# GYBHDHT.net
KiCad netlist of a schematic drawn in Altium Designer
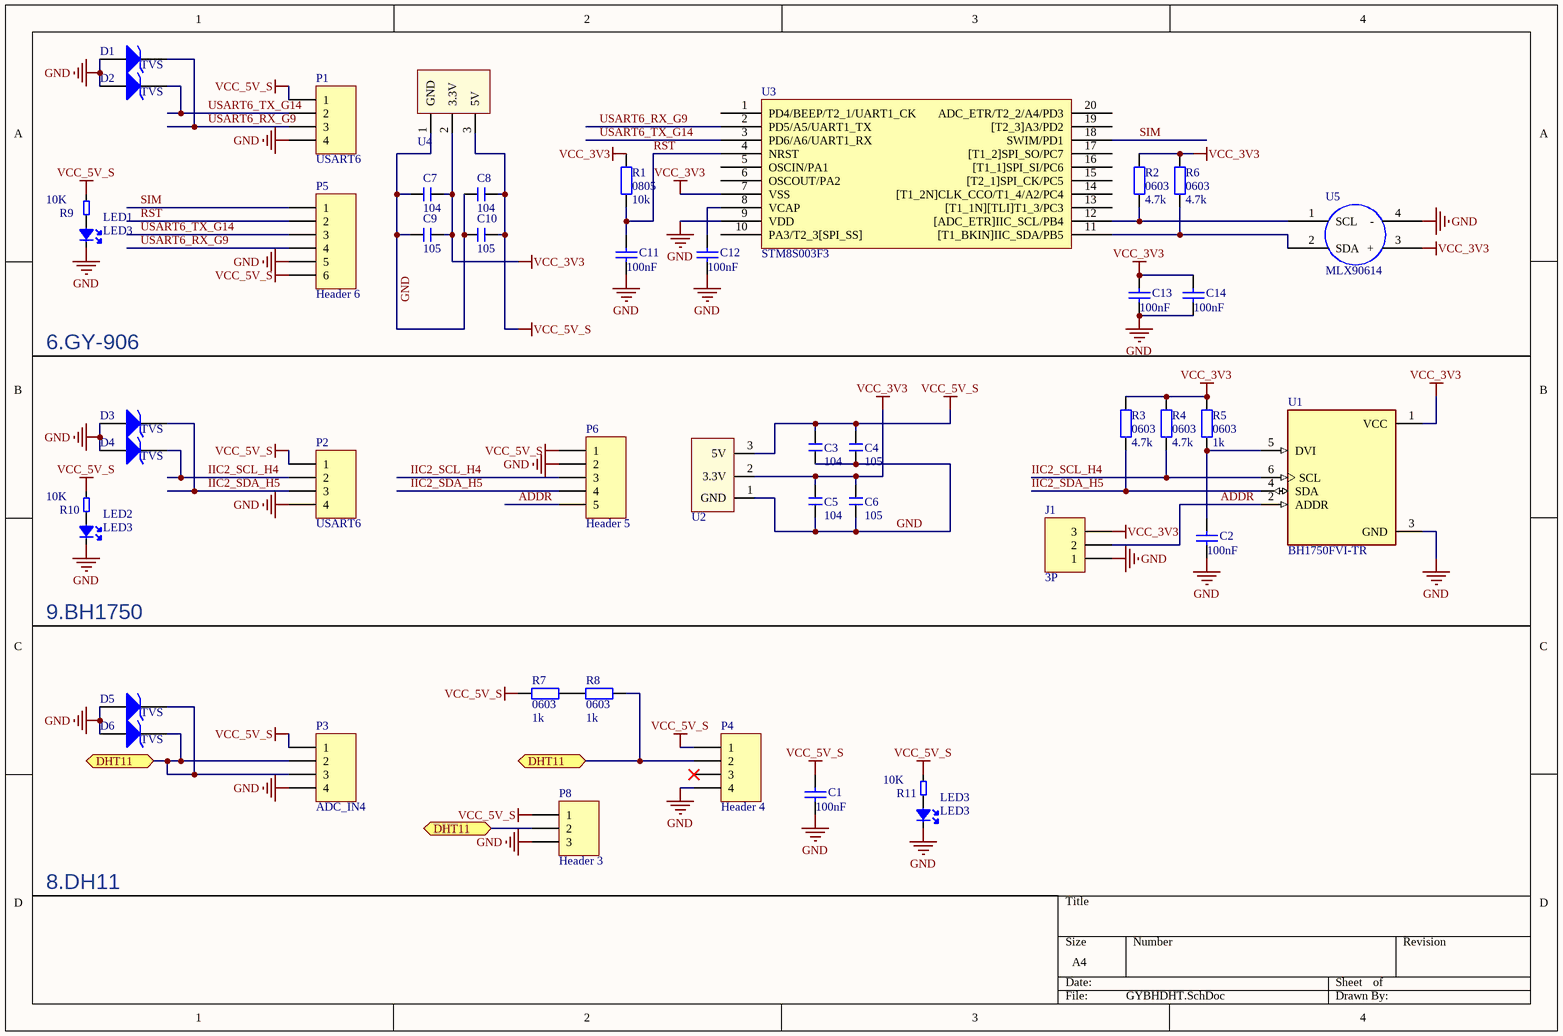
[diagram p0: GYBHDHT.SchDoc]

(export (version "E")
  (design (tool "Eeschema 10.0.6"))
  (components
    (comp (ref "C1")
      (value "100nF")
      (footprint "C 0603_L")
      (fields (field (name "Comment") "CAP"))
      (libsource (lib "QT") (part "CAP"))
    )
    (comp (ref "C2")
      (value "100nF")
      (footprint "C 0603_L")
      (fields (field (name "Comment") "CAP"))
      (libsource (lib "QT") (part "CAP"))
    )
    (comp (ref "C3")
      (value "104")
      (footprint "C 0603")
      (description "无极性贴片电容")
      (fields (field (name "版权归属") "源创客"))
      (libsource (lib "电阻-电容-电感") (part "C"))
    )
    (comp (ref "C4")
      (value "105")
      (footprint "C 0603")
      (description "无极性贴片电容")
      (fields (field (name "版权归属") "源创客"))
      (libsource (lib "电阻-电容-电感") (part "C"))
    )
    (comp (ref "C5")
      (value "104")
      (footprint "C 0603")
      (description "无极性贴片电容")
      (fields (field (name "版权归属") "源创客"))
      (libsource (lib "电阻-电容-电感") (part "C"))
    )
    (comp (ref "C6")
      (value "105")
      (footprint "C 0603")
      (description "无极性贴片电容")
      (fields (field (name "版权归属") "源创客"))
      (libsource (lib "电阻-电容-电感") (part "C"))
    )
    (comp (ref "C7")
      (value "104")
      (footprint "C 0603")
      (description "无极性贴片电容")
      (fields (field (name "版权归属") "源创客"))
      (libsource (lib "电阻-电容-电感") (part "C"))
    )
    (comp (ref "C8")
      (value "104")
      (footprint "C 0603")
      (description "无极性贴片电容")
      (fields (field (name "版权归属") "源创客"))
      (libsource (lib "电阻-电容-电感") (part "C"))
    )
    (comp (ref "C9")
      (value "105")
      (footprint "C 0603")
      (description "无极性贴片电容")
      (fields (field (name "版权归属") "源创客"))
      (libsource (lib "电阻-电容-电感") (part "C"))
    )
    (comp (ref "C10")
      (value "105")
      (footprint "C 0603")
      (description "无极性贴片电容")
      (fields (field (name "版权归属") "源创客"))
      (libsource (lib "电阻-电容-电感") (part "C"))
    )
    (comp (ref "C11")
      (value "100nF")
      (footprint "C 0603_L")
      (fields (field (name "Comment") "CAP"))
      (libsource (lib "QT") (part "CAP"))
    )
    (comp (ref "C12")
      (value "100nF")
      (footprint "C 0603_M")
      (fields (field (name "Comment") "CAP"))
      (libsource (lib "QT") (part "CAP"))
    )
    (comp (ref "C13")
      (value "100nF")
      (footprint "C 0603_M")
      (fields (field (name "Comment") "CAP"))
      (libsource (lib "QT") (part "CAP"))
    )
    (comp (ref "C14")
      (value "100nF")
      (footprint "C 0603_M")
      (fields (field (name "Comment") "CAP"))
      (libsource (lib "QT") (part "CAP"))
    )
    (comp (ref "D1")
      (value "TVS")
      (footprint "SOD-523")
      (description "High Conductance Fast Diode")
      (fields (field (name "PUBLISHER") "Altium Limited"))
      (libsource (lib "QT") (part "D"))
    )
    (comp (ref "D2")
      (value "TVS")
      (footprint "SOD-523")
      (description "High Conductance Fast Diode")
      (fields (field (name "PUBLISHER") "Altium Limited"))
      (libsource (lib "QT") (part "D"))
    )
    (comp (ref "D3")
      (value "TVS")
      (footprint "SOD-523")
      (description "High Conductance Fast Diode")
      (fields (field (name "PUBLISHER") "Altium Limited"))
      (libsource (lib "QT") (part "D"))
    )
    (comp (ref "D4")
      (value "TVS")
      (footprint "SOD-523")
      (description "High Conductance Fast Diode")
      (fields (field (name "PUBLISHER") "Altium Limited"))
      (libsource (lib "QT") (part "D"))
    )
    (comp (ref "D5")
      (value "TVS")
      (footprint "SOD-523")
      (description "High Conductance Fast Diode")
      (fields (field (name "PUBLISHER") "Altium Limited"))
      (libsource (lib "QT") (part "D"))
    )
    (comp (ref "D6")
      (value "TVS")
      (footprint "SOD-523")
      (description "High Conductance Fast Diode")
      (fields (field (name "PUBLISHER") "Altium Limited"))
      (libsource (lib "QT") (part "D"))
    )
    (comp (ref "J1") (value "3P") (footprint "3P") (libsource (lib "F1C100S") (part "3P")))
    (comp (ref "LED1")
      (value "LED3")
      (footprint "0603-led")
      (description "DIODE LED")
      (libsource (lib "HXT-SCH") (part "CP_DIOLED"))
    )
    (comp (ref "LED2")
      (value "LED3")
      (footprint "0603-led")
      (description "DIODE LED")
      (libsource (lib "HXT-SCH") (part "CP_DIOLED"))
    )
    (comp (ref "LED3")
      (value "LED3")
      (footprint "0603-led")
      (description "DIODE LED")
      (libsource (lib "HXT-SCH") (part "CP_DIOLED"))
    )
    (comp (ref "P1")
      (value "USART6")
      (footprint "KF2EDGK-2.54-WI-4P")
      (description "Header, 4-Pin")
      (fields (field (name "PUBLISHER") "Altium Limited"))
      (libsource (lib "QT") (part "Header 4"))
    )
    (comp (ref "P2")
      (value "USART6")
      (footprint "KF2EDGK-2.54-WI-4P")
      (description "Header, 4-Pin")
      (fields (field (name "PUBLISHER") "Altium Limited"))
      (libsource (lib "QT") (part "Header 4"))
    )
    (comp (ref "P3")
      (value "ADC_IN4")
      (footprint "KF2EDGK-2.54-WI-4P")
      (description "Header, 4-Pin")
      (fields (field (name "PUBLISHER") "Altium Limited"))
      (libsource (lib "QT") (part "Header 4"))
    )
    (comp (ref "P4")
      (value "Header 4")
      (footprint "HDR2.54-LI-4P")
      (description "Header, 4-Pin")
      (fields (field (name "PUBLISHER") "Altium Limited"))
      (libsource (lib "QT") (part "Header 4"))
    )
    (comp (ref "P5")
      (value "Header 6")
      (footprint "HDR2.54-LI-6P")
      (description "Header, 6-Pin")
      (fields (field (name "PUBLISHER") "Altium Limited"))
      (libsource (lib "QT") (part "Header 6"))
    )
    (comp (ref "P6")
      (value "Header 5")
      (footprint "HDR2.54-LI-5P")
      (description "Header, 5-Pin")
      (fields (field (name "PUBLISHER") "Altium Limited"))
      (libsource (lib "QT") (part "Header 5"))
    )
    (comp (ref "P8")
      (value "Header 3")
      (footprint "HDR2.54-LI-3P")
      (description "Header, 3-Pin")
      (fields (field (name "PUBLISHER") "Altium Limited"))
      (libsource (lib "QT") (part "Header 3"))
    )
    (comp (ref "R1")
      (value "0805")
      (footprint "R 0603")
      (description "Resistor")
      (fields (field (name "ALTIUM_VALUE") "10k") (field (name "PUBLISHER") "Altium Limited"))
      (libsource (lib "QT") (part "RES2"))
    )
    (comp (ref "R2")
      (value "0603")
      (footprint "R 0603")
      (description "Resistor")
      (fields (field (name "ALTIUM_VALUE") "4.7k") (field (name "PUBLISHER") "Altium Limited"))
      (libsource (lib "QT") (part "RES2"))
    )
    (comp (ref "R3")
      (value "0603")
      (footprint "R 0603")
      (description "Resistor")
      (fields (field (name "ALTIUM_VALUE") "4.7k") (field (name "PUBLISHER") "Altium Limited"))
      (libsource (lib "QT") (part "RES2"))
    )
    (comp (ref "R4")
      (value "0603")
      (footprint "R 0603")
      (description "Resistor")
      (fields (field (name "ALTIUM_VALUE") "4.7k") (field (name "PUBLISHER") "Altium Limited"))
      (libsource (lib "QT") (part "RES2"))
    )
    (comp (ref "R5")
      (value "0603")
      (footprint "R 0603")
      (description "Resistor")
      (fields (field (name "ALTIUM_VALUE") "1k") (field (name "PUBLISHER") "Altium Limited"))
      (libsource (lib "QT") (part "RES2"))
    )
    (comp (ref "R6")
      (value "0603")
      (footprint "R 0603")
      (description "Resistor")
      (fields (field (name "ALTIUM_VALUE") "4.7k") (field (name "PUBLISHER") "Altium Limited"))
      (libsource (lib "QT") (part "RES2"))
    )
    (comp (ref "R7")
      (value "0603")
      (footprint "R 0603")
      (description "Resistor")
      (fields (field (name "ALTIUM_VALUE") "1k") (field (name "PUBLISHER") "Altium Limited"))
      (libsource (lib "") (part "RES2_1"))
    )
    (comp (ref "R8")
      (value "0603")
      (footprint "R 0603")
      (description "Resistor")
      (fields (field (name "ALTIUM_VALUE") "1k") (field (name "PUBLISHER") "Altium Limited"))
      (libsource (lib "") (part "RES2_1"))
    )
    (comp (ref "R9") (value "10K") (footprint "0603") (libsource (lib "HXT-SCH") (part "RES2")))
    (comp (ref "R10") (value "10K") (footprint "0603") (libsource (lib "HXT-SCH") (part "RES2")))
    (comp (ref "R11") (value "10K") (footprint "0603") (libsource (lib "HXT-SCH") (part "RES2")))
    (comp (ref "U1")
      (value "BH1750FVI-TR")
      (footprint "XDCR_BH1750FVI-TR")
      (description "Optical Sensor Ambient 560nm IÂ²C 6-SMD, Flat Lead Exposed Pad")
      (fields (field (name "MF") "Rohm"))
      (libsource (lib "SnapEDAsch") (part "BH1750FVI-TR"))
    )
    (comp (ref "U2") (value "LM1117") (footprint "SOT23-3M") (libsource (lib "常用元件库") (part "LM1117")))
    (comp (ref "U3")
      (value "STM8S003F3")
      (footprint "TSSOP20")
      (description "8位STM单片机")
      (fields (field (name "版权归属") "源创客"))
      (libsource (lib "STM8系列单片机") (part "STM8S003F3"))
    )
    (comp (ref "U4") (value "LM1117") (footprint "SOT23-3M") (libsource (lib "") (part "LM1117_1")))
    (comp (ref "U5") (value "MLX90614") (footprint "MLX90614") (libsource (lib "常用元件库") (part "MLX90614")))
  )
  (nets
    (net (code "1") (name "/ADDR") (class "Default")
      (node (ref "J1") (pin "2") (pinfunction "2_2") (pintype "passive"))
      (node (ref "P6") (pin "5") (pinfunction "5_5") (pintype "passive"))
      (node (ref "U1") (pin "2") (pinfunction "ADDR_2") (pintype "input"))
    )
    (net (code "2") (name "/DHT11") (class "Default")
      (node (ref "D5") (pin "2") (pinfunction "K_2") (pintype "passive"))
      (node (ref "D6") (pin "2") (pinfunction "K_2") (pintype "passive"))
      (node (ref "P3") (pin "2") (pinfunction "2_2") (pintype "passive"))
      (node (ref "P3") (pin "3") (pinfunction "3_3") (pintype "passive"))
      (node (ref "P4") (pin "2") (pinfunction "2_2") (pintype "passive"))
      (node (ref "P8") (pin "2") (pinfunction "2_2") (pintype "passive"))
      (node (ref "R8") (pin "2") (pinfunction "2_2") (pintype "passive"))
    )
    (net (code "3") (name "/IIC2_SCL_H4") (class "Default")
      (node (ref "D4") (pin "2") (pinfunction "K_2") (pintype "passive"))
      (node (ref "P2") (pin "2") (pinfunction "2_2") (pintype "passive"))
      (node (ref "P6") (pin "3") (pinfunction "3_3") (pintype "passive"))
      (node (ref "R4") (pin "2") (pinfunction "2_2") (pintype "passive"))
      (node (ref "U1") (pin "6") (pinfunction "SCL_6") (pintype "input"))
    )
    (net (code "4") (name "/IIC2_SDA_H5") (class "Default")
      (node (ref "D3") (pin "2") (pinfunction "K_2") (pintype "passive"))
      (node (ref "P2") (pin "3") (pinfunction "3_3") (pintype "passive"))
      (node (ref "P6") (pin "4") (pinfunction "4_4") (pintype "passive"))
      (node (ref "R3") (pin "2") (pinfunction "2_2") (pintype "passive"))
      (node (ref "U1") (pin "4") (pinfunction "SDA_4") (pintype "bidirectional"))
    )
    (net (code "5") (name "/RST") (class "Default")
      (node (ref "C11") (pin "2") (pinfunction "2_2") (pintype "passive"))
      (node (ref "P5") (pin "2") (pinfunction "2_2") (pintype "passive"))
      (node (ref "R1") (pin "2") (pinfunction "2_2") (pintype "passive"))
      (node (ref "U3") (pin "4") (pinfunction "NRST_4") (pintype "passive"))
    )
    (net (code "6") (name "/SIM") (class "Default")
      (node (ref "P5") (pin "1") (pinfunction "1_1") (pintype "passive"))
      (node (ref "U3") (pin "18") (pinfunction "SWIM/PD1_18") (pintype "passive"))
    )
    (net (code "7") (name "/USART6_RX_G9") (class "Default")
      (node (ref "D1") (pin "2") (pinfunction "K_2") (pintype "passive"))
      (node (ref "P1") (pin "3") (pinfunction "3_3") (pintype "passive"))
      (node (ref "P5") (pin "4") (pinfunction "4_4") (pintype "passive"))
      (node (ref "U3") (pin "2") (pinfunction "PD5/A5/UART1_TX_2") (pintype "passive"))
    )
    (net (code "8") (name "/USART6_TX_G14") (class "Default")
      (node (ref "D2") (pin "2") (pinfunction "K_2") (pintype "passive"))
      (node (ref "P1") (pin "2") (pinfunction "2_2") (pintype "passive"))
      (node (ref "P5") (pin "3") (pinfunction "3_3") (pintype "passive"))
      (node (ref "U3") (pin "3") (pinfunction "PD6/A6/UART1_RX_3") (pintype "passive"))
    )
    (net (code "9") (name "GND") (class "Default")
      (node (ref "C1") (pin "1") (pinfunction "1_1") (pintype "passive"))
      (node (ref "C10") (pin "2") (pinfunction "2_2") (pintype "passive"))
      (node (ref "C11") (pin "1") (pinfunction "1_1") (pintype "passive"))
      (node (ref "C12") (pin "1") (pinfunction "1_1") (pintype "passive"))
      (node (ref "C13") (pin "1") (pinfunction "1_1") (pintype "passive"))
      (node (ref "C14") (pin "1") (pinfunction "1_1") (pintype "passive"))
      (node (ref "C2") (pin "1") (pinfunction "1_1") (pintype "passive"))
      (node (ref "C3") (pin "1") (pinfunction "1_1") (pintype "passive"))
      (node (ref "C4") (pin "2") (pinfunction "2_2") (pintype "passive"))
      (node (ref "C5") (pin "1") (pinfunction "1_1") (pintype "passive"))
      (node (ref "C6") (pin "2") (pinfunction "2_2") (pintype "passive"))
      (node (ref "C7") (pin "1") (pinfunction "1_1") (pintype "passive"))
      (node (ref "C8") (pin "1") (pinfunction "1_1") (pintype "passive"))
      (node (ref "C9") (pin "2") (pinfunction "2_2") (pintype "passive"))
      (node (ref "D1") (pin "1") (pinfunction "A_1") (pintype "passive"))
      (node (ref "D2") (pin "1") (pinfunction "A_1") (pintype "passive"))
      (node (ref "D3") (pin "1") (pinfunction "A_1") (pintype "passive"))
      (node (ref "D4") (pin "1") (pinfunction "A_1") (pintype "passive"))
      (node (ref "D5") (pin "1") (pinfunction "A_1") (pintype "passive"))
      (node (ref "D6") (pin "1") (pinfunction "A_1") (pintype "passive"))
      (node (ref "J1") (pin "1") (pinfunction "1_1") (pintype "passive"))
      (node (ref "LED1") (pin "2") (pinfunction "K_2") (pintype "passive"))
      (node (ref "LED2") (pin "2") (pinfunction "K_2") (pintype "passive"))
      (node (ref "LED3") (pin "2") (pinfunction "K_2") (pintype "passive"))
      (node (ref "P1") (pin "4") (pinfunction "4_4") (pintype "passive"))
      (node (ref "P2") (pin "4") (pinfunction "4_4") (pintype "passive"))
      (node (ref "P3") (pin "4") (pinfunction "4_4") (pintype "passive"))
      (node (ref "P4") (pin "4") (pinfunction "4_4") (pintype "passive"))
      (node (ref "P5") (pin "5") (pinfunction "5_5") (pintype "passive"))
      (node (ref "P6") (pin "2") (pinfunction "2_2") (pintype "passive"))
      (node (ref "P8") (pin "3") (pinfunction "3_3") (pintype "passive"))
      (node (ref "U1") (pin "3") (pinfunction "GND_3") (pintype "power_in"))
      (node (ref "U2") (pin "1") (pinfunction "GND_1") (pintype "passive"))
      (node (ref "U3") (pin "9") (pinfunction "VDD_9") (pintype "passive"))
      (node (ref "U4") (pin "1") (pinfunction "GND_1") (pintype "passive"))
      (node (ref "U5") (pin "4") (pinfunction "-_4") (pintype "passive"))
    )
    (net (code "10") (name "Net-(LED1-A)") (class "Default")
      (node (ref "LED1") (pin "1") (pinfunction "A_1") (pintype "passive"))
      (node (ref "R9") (pin "1") (pinfunction "1_1") (pintype "passive"))
    )
    (net (code "11") (name "Net-(LED2-A)") (class "Default")
      (node (ref "LED2") (pin "1") (pinfunction "A_1") (pintype "passive"))
      (node (ref "R10") (pin "1") (pinfunction "1_1") (pintype "passive"))
    )
    (net (code "12") (name "Net-(LED3-A)") (class "Default")
      (node (ref "LED3") (pin "1") (pinfunction "A_1") (pintype "passive"))
      (node (ref "R11") (pin "1") (pinfunction "1_1") (pintype "passive"))
    )
    (net (code "13") (name "Net-(R7-Pad2)") (class "Default")
      (node (ref "R7") (pin "2") (pinfunction "2_2") (pintype "passive"))
      (node (ref "R8") (pin "1") (pinfunction "1_1") (pintype "passive"))
    )
    (net (code "14") (name "Net-(U1-DVI)") (class "Default")
      (node (ref "C2") (pin "2") (pinfunction "2_2") (pintype "passive"))
      (node (ref "R5") (pin "2") (pinfunction "2_2") (pintype "passive"))
      (node (ref "U1") (pin "5") (pinfunction "DVI_5") (pintype "input"))
    )
    (net (code "15") (name "Net-(U3-VCAP)") (class "Default")
      (node (ref "C12") (pin "2") (pinfunction "2_2") (pintype "passive"))
      (node (ref "U3") (pin "8") (pinfunction "VCAP_8") (pintype "passive"))
    )
    (net (code "16") (name "Net-(U3-[ADC_ETR]IIC_SCL{slash}PB4)") (class "Default")
      (node (ref "R2") (pin "2") (pinfunction "2_2") (pintype "passive"))
      (node (ref "U3") (pin "12") (pinfunction "[ADC_ETR]IIC_SCL/PB4_12") (pintype "passive"))
      (node (ref "U5") (pin "1") (pinfunction "SCL_1") (pintype "passive"))
    )
    (net (code "17") (name "Net-(U3-[T1_BKIN]IIC_SDA{slash}PB5)") (class "Default")
      (node (ref "R6") (pin "2") (pinfunction "2_2") (pintype "passive"))
      (node (ref "U3") (pin "11") (pinfunction "[T1_BKIN]IIC_SDA/PB5_11") (pintype "passive"))
      (node (ref "U5") (pin "2") (pinfunction "SDA_2") (pintype "passive"))
    )
    (net (code "18") (name "VCC_3V3") (class "Default")
      (node (ref "C13") (pin "2") (pinfunction "2_2") (pintype "passive"))
      (node (ref "C14") (pin "2") (pinfunction "2_2") (pintype "passive"))
      (node (ref "C5") (pin "2") (pinfunction "2_2") (pintype "passive"))
      (node (ref "C6") (pin "1") (pinfunction "1_1") (pintype "passive"))
      (node (ref "C7") (pin "2") (pinfunction "2_2") (pintype "passive"))
      (node (ref "C9") (pin "1") (pinfunction "1_1") (pintype "passive"))
      (node (ref "J1") (pin "3") (pinfunction "3_3") (pintype "passive"))
      (node (ref "R1") (pin "1") (pinfunction "1_1") (pintype "passive"))
      (node (ref "R2") (pin "1") (pinfunction "1_1") (pintype "passive"))
      (node (ref "R3") (pin "1") (pinfunction "1_1") (pintype "passive"))
      (node (ref "R4") (pin "1") (pinfunction "1_1") (pintype "passive"))
      (node (ref "R5") (pin "1") (pinfunction "1_1") (pintype "passive"))
      (node (ref "R6") (pin "1") (pinfunction "1_1") (pintype "passive"))
      (node (ref "U1") (pin "1") (pinfunction "VCC_1") (pintype "power_in"))
      (node (ref "U2") (pin "2") (pinfunction "3.3V_2") (pintype "passive"))
      (node (ref "U3") (pin "7") (pinfunction "VSS_7") (pintype "passive"))
      (node (ref "U4") (pin "2") (pinfunction "3.3V_2") (pintype "passive"))
      (node (ref "U5") (pin "3") (pinfunction "+_3") (pintype "passive"))
    )
    (net (code "19") (name "VCC_5V_S") (class "Default")
      (node (ref "C1") (pin "2") (pinfunction "2_2") (pintype "passive"))
      (node (ref "C10") (pin "1") (pinfunction "1_1") (pintype "passive"))
      (node (ref "C3") (pin "2") (pinfunction "2_2") (pintype "passive"))
      (node (ref "C4") (pin "1") (pinfunction "1_1") (pintype "passive"))
      (node (ref "C8") (pin "2") (pinfunction "2_2") (pintype "passive"))
      (node (ref "P1") (pin "1") (pinfunction "1_1") (pintype "passive"))
      (node (ref "P2") (pin "1") (pinfunction "1_1") (pintype "passive"))
      (node (ref "P3") (pin "1") (pinfunction "1_1") (pintype "passive"))
      (node (ref "P4") (pin "1") (pinfunction "1_1") (pintype "passive"))
      (node (ref "P5") (pin "6") (pinfunction "6_6") (pintype "passive"))
      (node (ref "P6") (pin "1") (pinfunction "1_1") (pintype "passive"))
      (node (ref "P8") (pin "1") (pinfunction "1_1") (pintype "passive"))
      (node (ref "R10") (pin "2") (pinfunction "2_2") (pintype "passive"))
      (node (ref "R11") (pin "2") (pinfunction "2_2") (pintype "passive"))
      (node (ref "R7") (pin "1") (pinfunction "1_1") (pintype "passive"))
      (node (ref "R9") (pin "2") (pinfunction "2_2") (pintype "passive"))
      (node (ref "U2") (pin "3") (pinfunction "5V_3") (pintype "passive"))
      (node (ref "U4") (pin "3") (pinfunction "5V_3") (pintype "passive"))
    )
    (net (code "20") (name "unconnected-(P4-Pad3)") (class "Default")
      (node (ref "P4") (pin "3") (pinfunction "3_3") (pintype "passive+no_connect"))
    )
    (net (code "21") (name "unconnected-(U3-ADC_ETR{slash}T2_2{slash}A4{slash}PD3-Pad20)") (class "Default")
      (node (ref "U3") (pin "20") (pinfunction "ADC_ETR/T2_2/A4/PD3_20") (pintype "passive"))
    )
    (net (code "22") (name "unconnected-(U3-OSCIN{slash}PA1-Pad5)") (class "Default")
      (node (ref "U3") (pin "5") (pinfunction "OSCIN/PA1_5") (pintype "passive"))
    )
    (net (code "23") (name "unconnected-(U3-OSCOUT{slash}PA2-Pad6)") (class "Default")
      (node (ref "U3") (pin "6") (pinfunction "OSCOUT/PA2_6") (pintype "passive"))
    )
    (net (code "24") (name "unconnected-(U3-PA3{slash}T2_3[SPI_SS]-Pad10)") (class "Default")
      (node (ref "U3") (pin "10") (pinfunction "PA3/T2_3[SPI_SS]_10") (pintype "passive"))
    )
    (net (code "25") (name "unconnected-(U3-PD4{slash}BEEP{slash}T2_1{slash}UART1_CK-Pad1)") (class "Default")
      (node (ref "U3") (pin "1") (pinfunction "PD4/BEEP/T2_1/UART1_CK_1") (pintype "passive"))
    )
    (net (code "26") (name "unconnected-(U3-[T1_1N][TLI]T1_3{slash}PC3-Pad13)") (class "Default")
      (node (ref "U3") (pin "13") (pinfunction "[T1_1N][TLI]T1_3/PC3_13") (pintype "passive"))
    )
    (net (code "27") (name "unconnected-(U3-[T1_1]SPI_SI{slash}PC6-Pad16)") (class "Default")
      (node (ref "U3") (pin "16") (pinfunction "[T1_1]SPI_SI/PC6_16") (pintype "passive"))
    )
    (net (code "28") (name "unconnected-(U3-[T1_2N]CLK_CCO{slash}T1_4{slash}A2{slash}PC4-Pad14)") (class "Default")
      (node (ref "U3") (pin "14") (pinfunction "[T1_2N]CLK_CCO/T1_4/A2/PC4_14") (pintype "passive"))
    )
    (net (code "29") (name "unconnected-(U3-[T1_2]SPI_SO{slash}PC7-Pad17)") (class "Default")
      (node (ref "U3") (pin "17") (pinfunction "[T1_2]SPI_SO/PC7_17") (pintype "passive"))
    )
    (net (code "30") (name "unconnected-(U3-[T2_1]SPI_CK{slash}PC5-Pad15)") (class "Default")
      (node (ref "U3") (pin "15") (pinfunction "[T2_1]SPI_CK/PC5_15") (pintype "passive"))
    )
    (net (code "31") (name "unconnected-(U3-[T2_3]A3{slash}PD2-Pad19)") (class "Default")
      (node (ref "U3") (pin "19") (pinfunction "[T2_3]A3/PD2_19") (pintype "passive"))
    )
  )
)
